# Sheet.net
KiCad netlist of a schematic drawn in Altium Designer
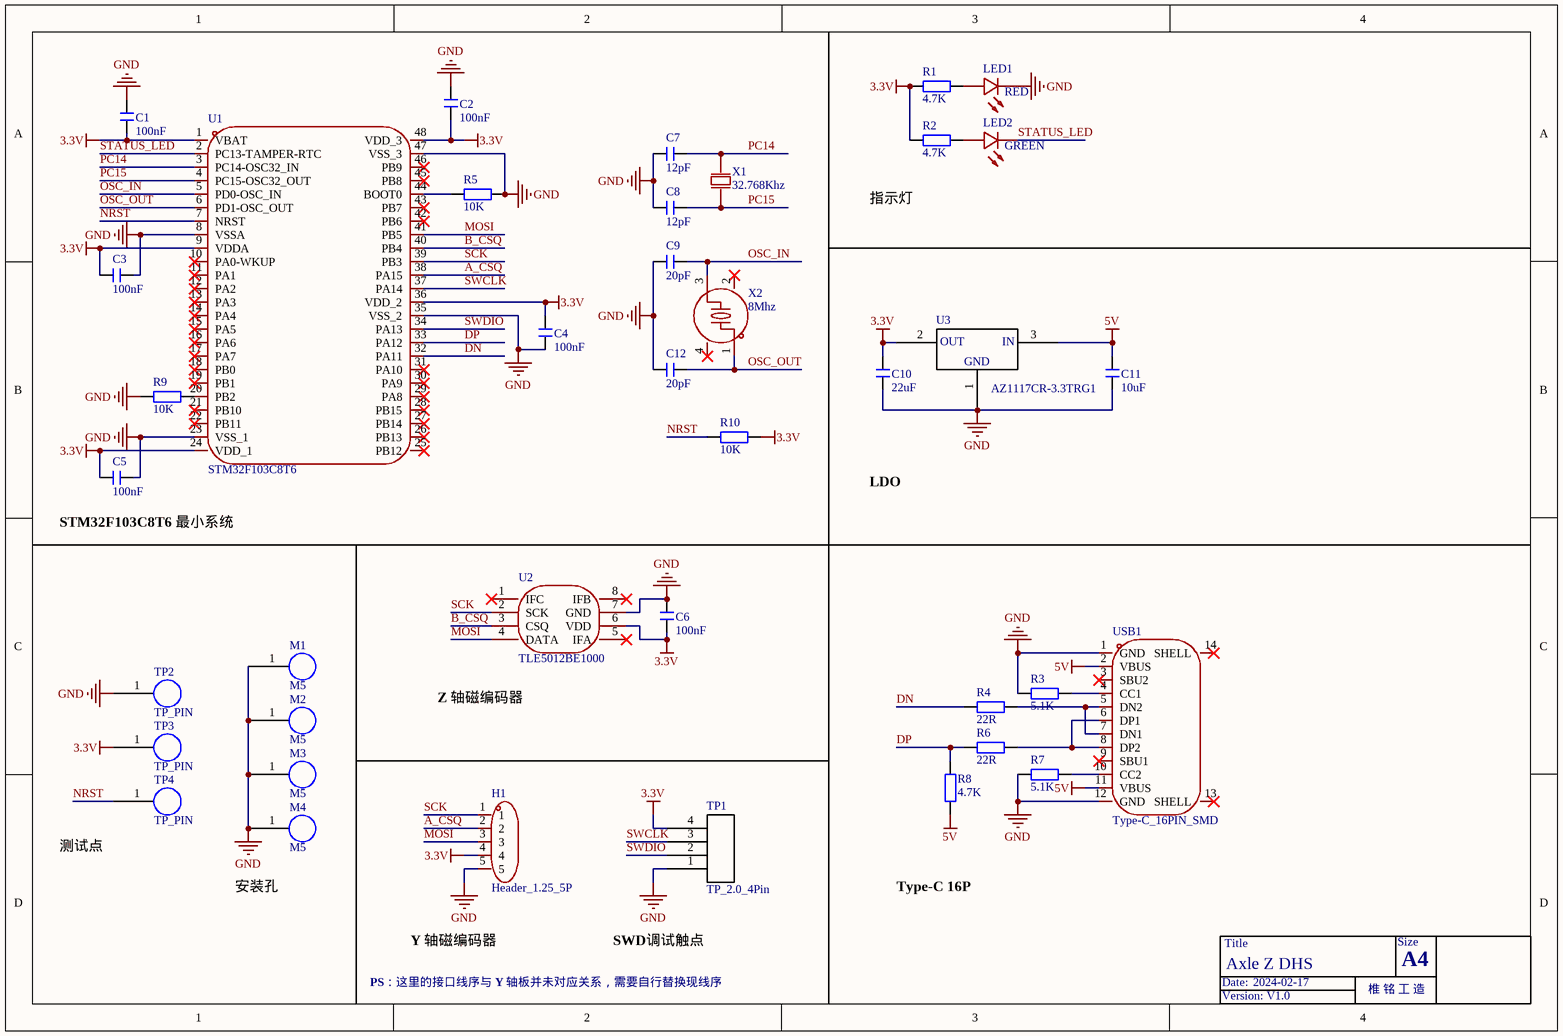
[diagram p0: Sheet.SchDoc]

(export (version "E")
  (design (tool "Eeschema 10.0.6"))
  (components
    (comp (ref "C1")
      (value "100nF")
      (footprint "C_0603_l")
      (description "MLCC 贴片独石电容")
      (libsource (lib "电阻-电容-电感") (part "C"))
    )
    (comp (ref "C2")
      (value "100nF")
      (footprint "C_0603_l")
      (description "MLCC 贴片独石电容")
      (libsource (lib "电阻-电容-电感") (part "C"))
    )
    (comp (ref "C3")
      (value "100nF")
      (footprint "C_0603_l")
      (description "MLCC 贴片独石电容")
      (libsource (lib "电阻-电容-电感") (part "C"))
    )
    (comp (ref "C4")
      (value "100nF")
      (footprint "C_0603_l")
      (description "MLCC 贴片独石电容")
      (libsource (lib "电阻-电容-电感") (part "C"))
    )
    (comp (ref "C5")
      (value "100nF")
      (footprint "C_0603_l")
      (description "MLCC 贴片独石电容")
      (libsource (lib "电阻-电容-电感") (part "C"))
    )
    (comp (ref "C6")
      (value "100nF")
      (footprint "C_0603_l")
      (description "MLCC 贴片独石电容")
      (libsource (lib "电阻-电容-电感") (part "C"))
    )
    (comp (ref "C7")
      (value "12pF")
      (footprint "C_0603_l")
      (description "MLCC 贴片独石电容")
      (libsource (lib "电阻-电容-电感") (part "C"))
    )
    (comp (ref "C8")
      (value "12pF")
      (footprint "C_0603_l")
      (description "MLCC 贴片独石电容")
      (libsource (lib "电阻-电容-电感") (part "C"))
    )
    (comp (ref "C9")
      (value "20pF")
      (footprint "C_0603_l")
      (description "MLCC 贴片独石电容")
      (libsource (lib "电阻-电容-电感") (part "C"))
    )
    (comp (ref "C10")
      (value "22uF")
      (footprint "C_0603_l")
      (description "MLCC 贴片独石电容")
      (libsource (lib "电阻-电容-电感") (part "C"))
    )
    (comp (ref "C11")
      (value "10uF")
      (footprint "C_0603_l")
      (description "MLCC 贴片独石电容")
      (libsource (lib "电阻-电容-电感") (part "C"))
    )
    (comp (ref "C12")
      (value "20pF")
      (footprint "C_0603_l")
      (description "MLCC 贴片独石电容")
      (libsource (lib "电阻-电容-电感") (part "C"))
    )
    (comp (ref "H1")
      (value "Header_1.25_5P")
      (footprint "PH_1.25_5P")
      (description "1.25mm 接插件")
      (libsource (lib "连接器") (part "Header_1.25_5P"))
    )
    (comp (ref "LED1")
      (value "RED")
      (footprint "LED_0603")
      (description "贴片发光二极管")
      (libsource (lib "光电器件") (part "SMD_LED"))
    )
    (comp (ref "LED2")
      (value "GREEN")
      (footprint "LED_0603")
      (description "贴片发光二极管")
      (libsource (lib "光电器件") (part "SMD_LED"))
    )
    (comp (ref "M1")
      (value "M5")
      (footprint "M5")
      (description "M5 螺丝安装孔")
      (libsource (lib "其它") (part "M5"))
    )
    (comp (ref "M2")
      (value "M5")
      (footprint "M5")
      (description "M5 螺丝安装孔")
      (libsource (lib "其它") (part "M5"))
    )
    (comp (ref "M3")
      (value "M5")
      (footprint "M5")
      (description "M5 螺丝安装孔")
      (libsource (lib "其它") (part "M5"))
    )
    (comp (ref "M4")
      (value "M5")
      (footprint "M5")
      (description "M5 螺丝安装孔")
      (libsource (lib "其它") (part "M5"))
    )
    (comp (ref "R1")
      (value "4.7K")
      (footprint "R_0603_L")
      (description "贴片电阻")
      (libsource (lib "电阻-电容-电感") (part "R"))
    )
    (comp (ref "R2")
      (value "4.7K")
      (footprint "R_0603_L")
      (description "贴片电阻")
      (libsource (lib "电阻-电容-电感") (part "R"))
    )
    (comp (ref "R3")
      (value "5.1K")
      (footprint "R_0603_L")
      (description "贴片电阻")
      (libsource (lib "电阻-电容-电感") (part "R"))
    )
    (comp (ref "R4")
      (value "22R")
      (footprint "R_0603_L")
      (description "贴片电阻")
      (libsource (lib "电阻-电容-电感") (part "R"))
    )
    (comp (ref "R5")
      (value "10K")
      (footprint "R_0603_L")
      (description "贴片电阻")
      (libsource (lib "电阻-电容-电感") (part "R"))
    )
    (comp (ref "R6")
      (value "22R")
      (footprint "R_0603_L")
      (description "贴片电阻")
      (libsource (lib "电阻-电容-电感") (part "R"))
    )
    (comp (ref "R7")
      (value "5.1K")
      (footprint "R_0603_L")
      (description "贴片电阻")
      (libsource (lib "电阻-电容-电感") (part "R"))
    )
    (comp (ref "R8")
      (value "4.7K")
      (footprint "R_0603_L")
      (description "贴片电阻")
      (libsource (lib "电阻-电容-电感") (part "R"))
    )
    (comp (ref "R9")
      (value "10K")
      (footprint "R_0603_L")
      (description "贴片电阻")
      (libsource (lib "电阻-电容-电感") (part "R"))
    )
    (comp (ref "R10")
      (value "10K")
      (footprint "R_0603_L")
      (description "贴片电阻")
      (libsource (lib "电阻-电容-电感") (part "R"))
    )
    (comp (ref "TP1")
      (value "TP_2.0_4Pin")
      (footprint "TP_2.0_4PIN_HOLE")
      (description "2.0mm 间距调试点")
      (libsource (lib "其它") (part "TP_2.0_4Pin"))
    )
    (comp (ref "TP2")
      (value "TP_PIN")
      (footprint "TP_PIN_1.2")
      (description "单点测试点")
      (libsource (lib "其它") (part "TP_PIN"))
    )
    (comp (ref "TP3")
      (value "TP_PIN")
      (footprint "TP_PIN_1.2")
      (description "单点测试点")
      (libsource (lib "其它") (part "TP_PIN"))
    )
    (comp (ref "TP4")
      (value "TP_PIN")
      (footprint "TP_PIN_1.2")
      (description "单点测试点")
      (libsource (lib "其它") (part "TP_PIN"))
    )
    (comp (ref "U1")
      (value "STM32F103C8T6")
      (footprint "LQFP_48")
      (libsource (lib "STM32-系列单片机") (part "STM32F103C8T6"))
    )
    (comp (ref "U2")
      (value "TLE5012BE1000")
      (footprint "SO-8")
      (description "采用巨磁电阻的角度传感器")
      (libsource (lib "位置传感器") (part "TLE5012BE1000"))
    )
    (comp (ref "U3")
      (value "AZ1117CR-3.3TRG1")
      (footprint "SOT_89_3")
      (description "3.3V 线性稳压器")
      (libsource (lib "电源管理芯片") (part "AZ1117CR-3.3TRG1"))
    )
    (comp (ref "USB1")
      (value "Type-C_16PIN_SMD")
      (footprint "Type-C_16PIN_SMD")
      (description "16Pin 卧贴 Type-C USB 连接器")
      (libsource (lib "连接器") (part "Type-C_16PIN_SMD"))
    )
    (comp (ref "X1")
      (value "32.768Khz")
      (footprint "SMD_L3.2_W1.5_2P")
      (description "32.768Khz 两脚 无源 贴片晶振")
      (libsource (lib "无源晶振") (part "无源晶振-32.768K-2P"))
    )
    (comp (ref "X2")
      (value "8Mhz")
      (footprint "SMD_L3.2_W2.5_4P")
      (description "8Mhz 四脚 无源 贴片晶振")
      (libsource (lib "无源晶振") (part "无源晶振-8Mhz-4P"))
    )
  )
  (nets
    (net (code "1") (name "/A_CSQ") (class "Default")
      (node (ref "H1") (pin "2") (pinfunction "2_2") (pintype "passive"))
      (node (ref "U1") (pin "38") (pinfunction "PA15_38") (pintype "passive"))
    )
    (net (code "2") (name "/B_CSQ") (class "Default")
      (node (ref "U1") (pin "40") (pinfunction "PB4_40") (pintype "passive"))
      (node (ref "U2") (pin "3") (pinfunction "CSQ_3") (pintype "passive"))
    )
    (net (code "3") (name "/DN") (class "Default")
      (node (ref "R4") (pin "1") (pinfunction "1_1") (pintype "passive"))
      (node (ref "U1") (pin "32") (pinfunction "PA11_32") (pintype "passive"))
    )
    (net (code "4") (name "/DP") (class "Default")
      (node (ref "R6") (pin "1") (pinfunction "1_1") (pintype "passive"))
      (node (ref "R8") (pin "2") (pinfunction "2_2") (pintype "passive"))
      (node (ref "U1") (pin "33") (pinfunction "PA12_33") (pintype "passive"))
    )
    (net (code "5") (name "/MOSI") (class "Default")
      (node (ref "H1") (pin "3") (pinfunction "3_3") (pintype "passive"))
      (node (ref "U1") (pin "41") (pinfunction "PB5_41") (pintype "passive"))
      (node (ref "U2") (pin "4") (pinfunction "DATA_4") (pintype "passive"))
    )
    (net (code "6") (name "/NRST") (class "Default")
      (node (ref "R10") (pin "1") (pinfunction "1_1") (pintype "passive"))
      (node (ref "TP4") (pin "1") (pintype "passive"))
      (node (ref "U1") (pin "7") (pinfunction "NRST_7") (pintype "passive"))
    )
    (net (code "7") (name "/OSC_IN") (class "Default")
      (node (ref "C9") (pin "1") (pinfunction "1_1") (pintype "passive"))
      (node (ref "U1") (pin "5") (pinfunction "PD0-OSC_IN_5") (pintype "passive"))
      (node (ref "X2") (pin "3") (pinfunction "3_3") (pintype "passive"))
    )
    (net (code "8") (name "/OSC_OUT") (class "Default")
      (node (ref "C12") (pin "1") (pinfunction "1_1") (pintype "passive"))
      (node (ref "U1") (pin "6") (pinfunction "PD1-OSC_OUT_6") (pintype "passive"))
      (node (ref "X2") (pin "1") (pinfunction "1_1") (pintype "passive"))
    )
    (net (code "9") (name "/PC14") (class "Default")
      (node (ref "C7") (pin "1") (pinfunction "1_1") (pintype "passive"))
      (node (ref "U1") (pin "3") (pinfunction "PC14-OSC32_IN_3") (pintype "passive"))
      (node (ref "X1") (pin "2") (pinfunction "OSC2_2") (pintype "passive"))
    )
    (net (code "10") (name "/PC15") (class "Default")
      (node (ref "C8") (pin "1") (pinfunction "1_1") (pintype "passive"))
      (node (ref "U1") (pin "4") (pinfunction "PC15-OSC32_OUT_4") (pintype "passive"))
      (node (ref "X1") (pin "1") (pinfunction "OSC1_1") (pintype "passive"))
    )
    (net (code "11") (name "/SCK") (class "Default")
      (node (ref "H1") (pin "1") (pinfunction "1_1") (pintype "passive"))
      (node (ref "U1") (pin "39") (pinfunction "PB3_39") (pintype "passive"))
      (node (ref "U2") (pin "2") (pinfunction "SCK_2") (pintype "passive"))
    )
    (net (code "12") (name "/STATUS_LED") (class "Default")
      (node (ref "LED2") (pin "1") (pinfunction "K_1") (pintype "passive"))
      (node (ref "U1") (pin "2") (pinfunction "PC13-TAMPER-RTC_2") (pintype "passive"))
    )
    (net (code "13") (name "/SWCLK") (class "Default")
      (node (ref "TP1") (pin "3") (pintype "passive"))
      (node (ref "U1") (pin "37") (pinfunction "PA14_37") (pintype "passive"))
    )
    (net (code "14") (name "/SWDIO") (class "Default")
      (node (ref "TP1") (pin "2") (pintype "passive"))
      (node (ref "U1") (pin "34") (pinfunction "PA13_34") (pintype "passive"))
    )
    (net (code "15") (name "3.3V") (class "Default")
      (node (ref "C1") (pin "1") (pinfunction "1_1") (pintype "passive"))
      (node (ref "C10") (pin "2") (pinfunction "2_2") (pintype "passive"))
      (node (ref "C2") (pin "1") (pinfunction "1_1") (pintype "passive"))
      (node (ref "C3") (pin "2") (pinfunction "2_2") (pintype "passive"))
      (node (ref "C4") (pin "2") (pinfunction "2_2") (pintype "passive"))
      (node (ref "C5") (pin "2") (pinfunction "2_2") (pintype "passive"))
      (node (ref "C6") (pin "1") (pinfunction "1_1") (pintype "passive"))
      (node (ref "H1") (pin "4") (pinfunction "4_4") (pintype "passive"))
      (node (ref "R1") (pin "1") (pinfunction "1_1") (pintype "passive"))
      (node (ref "R10") (pin "2") (pinfunction "2_2") (pintype "passive"))
      (node (ref "R2") (pin "1") (pinfunction "1_1") (pintype "passive"))
      (node (ref "TP1") (pin "4") (pintype "passive"))
      (node (ref "TP3") (pin "1") (pintype "passive"))
      (node (ref "U1") (pin "1") (pinfunction "VBAT_1") (pintype "passive"))
      (node (ref "U1") (pin "24") (pinfunction "VDD_1_24") (pintype "passive"))
      (node (ref "U1") (pin "36") (pinfunction "VDD_2_36") (pintype "passive"))
      (node (ref "U1") (pin "48") (pinfunction "VDD_3_48") (pintype "passive"))
      (node (ref "U1") (pin "9") (pinfunction "VDDA_9") (pintype "passive"))
      (node (ref "U2") (pin "6") (pinfunction "VDD_6") (pintype "passive"))
      (node (ref "U3") (pin "2") (pintype "passive"))
    )
    (net (code "16") (name "5V") (class "Default")
      (node (ref "C11") (pin "2") (pinfunction "2_2") (pintype "passive"))
      (node (ref "R8") (pin "1") (pinfunction "1_1") (pintype "passive"))
      (node (ref "U3") (pin "3") (pintype "passive"))
      (node (ref "USB1") (pin "11") (pinfunction "VBUS_11") (pintype "passive"))
      (node (ref "USB1") (pin "2") (pinfunction "VBUS_2") (pintype "passive"))
    )
    (net (code "17") (name "GND") (class "Default")
      (node (ref "C1") (pin "2") (pinfunction "2_2") (pintype "passive"))
      (node (ref "C10") (pin "1") (pinfunction "1_1") (pintype "passive"))
      (node (ref "C11") (pin "1") (pinfunction "1_1") (pintype "passive"))
      (node (ref "C12") (pin "2") (pinfunction "2_2") (pintype "passive"))
      (node (ref "C2") (pin "2") (pinfunction "2_2") (pintype "passive"))
      (node (ref "C3") (pin "1") (pinfunction "1_1") (pintype "passive"))
      (node (ref "C4") (pin "1") (pinfunction "1_1") (pintype "passive"))
      (node (ref "C5") (pin "1") (pinfunction "1_1") (pintype "passive"))
      (node (ref "C6") (pin "2") (pinfunction "2_2") (pintype "passive"))
      (node (ref "C7") (pin "2") (pinfunction "2_2") (pintype "passive"))
      (node (ref "C8") (pin "2") (pinfunction "2_2") (pintype "passive"))
      (node (ref "C9") (pin "2") (pinfunction "2_2") (pintype "passive"))
      (node (ref "H1") (pin "5") (pinfunction "5_5") (pintype "passive"))
      (node (ref "LED1") (pin "1") (pinfunction "K_1") (pintype "passive"))
      (node (ref "M1") (pin "1") (pintype "passive"))
      (node (ref "M2") (pin "1") (pintype "passive"))
      (node (ref "M3") (pin "1") (pintype "passive"))
      (node (ref "M4") (pin "1") (pintype "passive"))
      (node (ref "R3") (pin "1") (pinfunction "1_1") (pintype "passive"))
      (node (ref "R5") (pin "2") (pinfunction "2_2") (pintype "passive"))
      (node (ref "R7") (pin "1") (pinfunction "1_1") (pintype "passive"))
      (node (ref "R9") (pin "2") (pinfunction "2_2") (pintype "passive"))
      (node (ref "TP1") (pin "1") (pintype "passive"))
      (node (ref "TP2") (pin "1") (pintype "passive"))
      (node (ref "U1") (pin "23") (pinfunction "VSS_1_23") (pintype "passive"))
      (node (ref "U1") (pin "35") (pinfunction "VSS_2_35") (pintype "passive"))
      (node (ref "U1") (pin "47") (pinfunction "VSS_3_47") (pintype "passive"))
      (node (ref "U1") (pin "8") (pinfunction "VSSA_8") (pintype "passive"))
      (node (ref "U2") (pin "7") (pinfunction "GND_7") (pintype "passive"))
      (node (ref "U3") (pin "1") (pintype "passive"))
      (node (ref "USB1") (pin "1") (pinfunction "GND_1") (pintype "passive"))
      (node (ref "USB1") (pin "12") (pinfunction "GND_12") (pintype "passive"))
    )
    (net (code "18") (name "Net-(LED1-A)") (class "Default")
      (node (ref "LED1") (pin "2") (pinfunction "A_2") (pintype "passive"))
      (node (ref "R1") (pin "2") (pinfunction "2_2") (pintype "passive"))
    )
    (net (code "19") (name "Net-(LED2-A)") (class "Default")
      (node (ref "LED2") (pin "2") (pinfunction "A_2") (pintype "passive"))
      (node (ref "R2") (pin "2") (pinfunction "2_2") (pintype "passive"))
    )
    (net (code "20") (name "Net-(U1-BOOT0)") (class "Default")
      (node (ref "R5") (pin "1") (pinfunction "1_1") (pintype "passive"))
      (node (ref "U1") (pin "44") (pinfunction "BOOT0_44") (pintype "passive"))
    )
    (net (code "21") (name "Net-(U1-PB2)") (class "Default")
      (node (ref "R9") (pin "1") (pinfunction "1_1") (pintype "passive"))
      (node (ref "U1") (pin "20") (pinfunction "PB2_20") (pintype "passive"))
    )
    (net (code "22") (name "Net-(USB1-CC1)") (class "Default")
      (node (ref "R3") (pin "2") (pinfunction "2_2") (pintype "passive"))
      (node (ref "USB1") (pin "4") (pinfunction "CC1_4") (pintype "passive"))
    )
    (net (code "23") (name "Net-(USB1-CC2)") (class "Default")
      (node (ref "R7") (pin "2") (pinfunction "2_2") (pintype "passive"))
      (node (ref "USB1") (pin "10") (pinfunction "CC2_10") (pintype "passive"))
    )
    (net (code "24") (name "Net-(USB1-DN1)") (class "Default")
      (node (ref "R4") (pin "2") (pinfunction "2_2") (pintype "passive"))
      (node (ref "USB1") (pin "5") (pinfunction "DN2_5") (pintype "passive"))
      (node (ref "USB1") (pin "7") (pinfunction "DN1_7") (pintype "passive"))
    )
    (net (code "25") (name "Net-(USB1-DP1)") (class "Default")
      (node (ref "R6") (pin "2") (pinfunction "2_2") (pintype "passive"))
      (node (ref "USB1") (pin "6") (pinfunction "DP1_6") (pintype "passive"))
      (node (ref "USB1") (pin "8") (pinfunction "DP2_8") (pintype "passive"))
    )
    (net (code "26") (name "unconnected-(U1-PA0-WKUP-Pad10)") (class "Default")
      (node (ref "U1") (pin "10") (pinfunction "PA0-WKUP_10") (pintype "passive+no_connect"))
    )
    (net (code "27") (name "unconnected-(U1-PA1-Pad11)") (class "Default")
      (node (ref "U1") (pin "11") (pinfunction "PA1_11") (pintype "passive+no_connect"))
    )
    (net (code "28") (name "unconnected-(U1-PA2-Pad12)") (class "Default")
      (node (ref "U1") (pin "12") (pinfunction "PA2_12") (pintype "passive+no_connect"))
    )
    (net (code "29") (name "unconnected-(U1-PA3-Pad13)") (class "Default")
      (node (ref "U1") (pin "13") (pinfunction "PA3_13") (pintype "passive+no_connect"))
    )
    (net (code "30") (name "unconnected-(U1-PA4-Pad14)") (class "Default")
      (node (ref "U1") (pin "14") (pinfunction "PA4_14") (pintype "passive+no_connect"))
    )
    (net (code "31") (name "unconnected-(U1-PA5-Pad15)") (class "Default")
      (node (ref "U1") (pin "15") (pinfunction "PA5_15") (pintype "passive+no_connect"))
    )
    (net (code "32") (name "unconnected-(U1-PA6-Pad16)") (class "Default")
      (node (ref "U1") (pin "16") (pinfunction "PA6_16") (pintype "passive+no_connect"))
    )
    (net (code "33") (name "unconnected-(U1-PA7-Pad17)") (class "Default")
      (node (ref "U1") (pin "17") (pinfunction "PA7_17") (pintype "passive+no_connect"))
    )
    (net (code "34") (name "unconnected-(U1-PA8-Pad29)") (class "Default")
      (node (ref "U1") (pin "29") (pinfunction "PA8_29") (pintype "passive+no_connect"))
    )
    (net (code "35") (name "unconnected-(U1-PA9-Pad30)") (class "Default")
      (node (ref "U1") (pin "30") (pinfunction "PA9_30") (pintype "passive+no_connect"))
    )
    (net (code "36") (name "unconnected-(U1-PA10-Pad31)") (class "Default")
      (node (ref "U1") (pin "31") (pinfunction "PA10_31") (pintype "passive+no_connect"))
    )
    (net (code "37") (name "unconnected-(U1-PB0-Pad18)") (class "Default")
      (node (ref "U1") (pin "18") (pinfunction "PB0_18") (pintype "passive+no_connect"))
    )
    (net (code "38") (name "unconnected-(U1-PB1-Pad19)") (class "Default")
      (node (ref "U1") (pin "19") (pinfunction "PB1_19") (pintype "passive+no_connect"))
    )
    (net (code "39") (name "unconnected-(U1-PB6-Pad42)") (class "Default")
      (node (ref "U1") (pin "42") (pinfunction "PB6_42") (pintype "passive+no_connect"))
    )
    (net (code "40") (name "unconnected-(U1-PB7-Pad43)") (class "Default")
      (node (ref "U1") (pin "43") (pinfunction "PB7_43") (pintype "passive+no_connect"))
    )
    (net (code "41") (name "unconnected-(U1-PB8-Pad45)") (class "Default")
      (node (ref "U1") (pin "45") (pinfunction "PB8_45") (pintype "passive+no_connect"))
    )
    (net (code "42") (name "unconnected-(U1-PB9-Pad46)") (class "Default")
      (node (ref "U1") (pin "46") (pinfunction "PB9_46") (pintype "passive+no_connect"))
    )
    (net (code "43") (name "unconnected-(U1-PB10-Pad21)") (class "Default")
      (node (ref "U1") (pin "21") (pinfunction "PB10_21") (pintype "passive+no_connect"))
    )
    (net (code "44") (name "unconnected-(U1-PB11-Pad22)") (class "Default")
      (node (ref "U1") (pin "22") (pinfunction "PB11_22") (pintype "passive+no_connect"))
    )
    (net (code "45") (name "unconnected-(U1-PB12-Pad25)") (class "Default")
      (node (ref "U1") (pin "25") (pinfunction "PB12_25") (pintype "passive+no_connect"))
    )
    (net (code "46") (name "unconnected-(U1-PB13-Pad26)") (class "Default")
      (node (ref "U1") (pin "26") (pinfunction "PB13_26") (pintype "passive+no_connect"))
    )
    (net (code "47") (name "unconnected-(U1-PB14-Pad27)") (class "Default")
      (node (ref "U1") (pin "27") (pinfunction "PB14_27") (pintype "passive+no_connect"))
    )
    (net (code "48") (name "unconnected-(U1-PB15-Pad28)") (class "Default")
      (node (ref "U1") (pin "28") (pinfunction "PB15_28") (pintype "passive+no_connect"))
    )
    (net (code "49") (name "unconnected-(U2-IFA-Pad5)") (class "Default")
      (node (ref "U2") (pin "5") (pinfunction "IFA_5") (pintype "passive+no_connect"))
    )
    (net (code "50") (name "unconnected-(U2-IFB-Pad8)") (class "Default")
      (node (ref "U2") (pin "8") (pinfunction "IFB_8") (pintype "passive+no_connect"))
    )
    (net (code "51") (name "unconnected-(U2-IFC-Pad1)") (class "Default")
      (node (ref "U2") (pin "1") (pinfunction "IFC_1") (pintype "passive+no_connect"))
    )
    (net (code "52") (name "unconnected-(USB1-SBU1-Pad9)") (class "Default")
      (node (ref "USB1") (pin "9") (pinfunction "SBU1_9") (pintype "passive+no_connect"))
    )
    (net (code "53") (name "unconnected-(USB1-SBU2-Pad3)") (class "Default")
      (node (ref "USB1") (pin "3") (pinfunction "SBU2_3") (pintype "passive+no_connect"))
    )
    (net (code "54") (name "unconnected-(USB1-SHELL-Pad13)") (class "Default")
      (node (ref "USB1") (pin "13") (pinfunction "SHELL_13") (pintype "passive+no_connect"))
    )
    (net (code "55") (name "unconnected-(USB1-SHELL-Pad14)") (class "Default")
      (node (ref "USB1") (pin "14") (pinfunction "SHELL_14") (pintype "passive+no_connect"))
    )
    (net (code "56") (name "unconnected-(X2-GND-Pad2)") (class "Default")
      (node (ref "X2") (pin "2") (pinfunction "GND_2") (pintype "passive+no_connect"))
    )
    (net (code "57") (name "unconnected-(X2-GND-Pad4)") (class "Default")
      (node (ref "X2") (pin "4") (pinfunction "GND_4") (pintype "passive+no_connect"))
    )
  )
)
